# MultiWiiChassis_hex_power.net
KiCad netlist of a schematic drawn in EAGLE
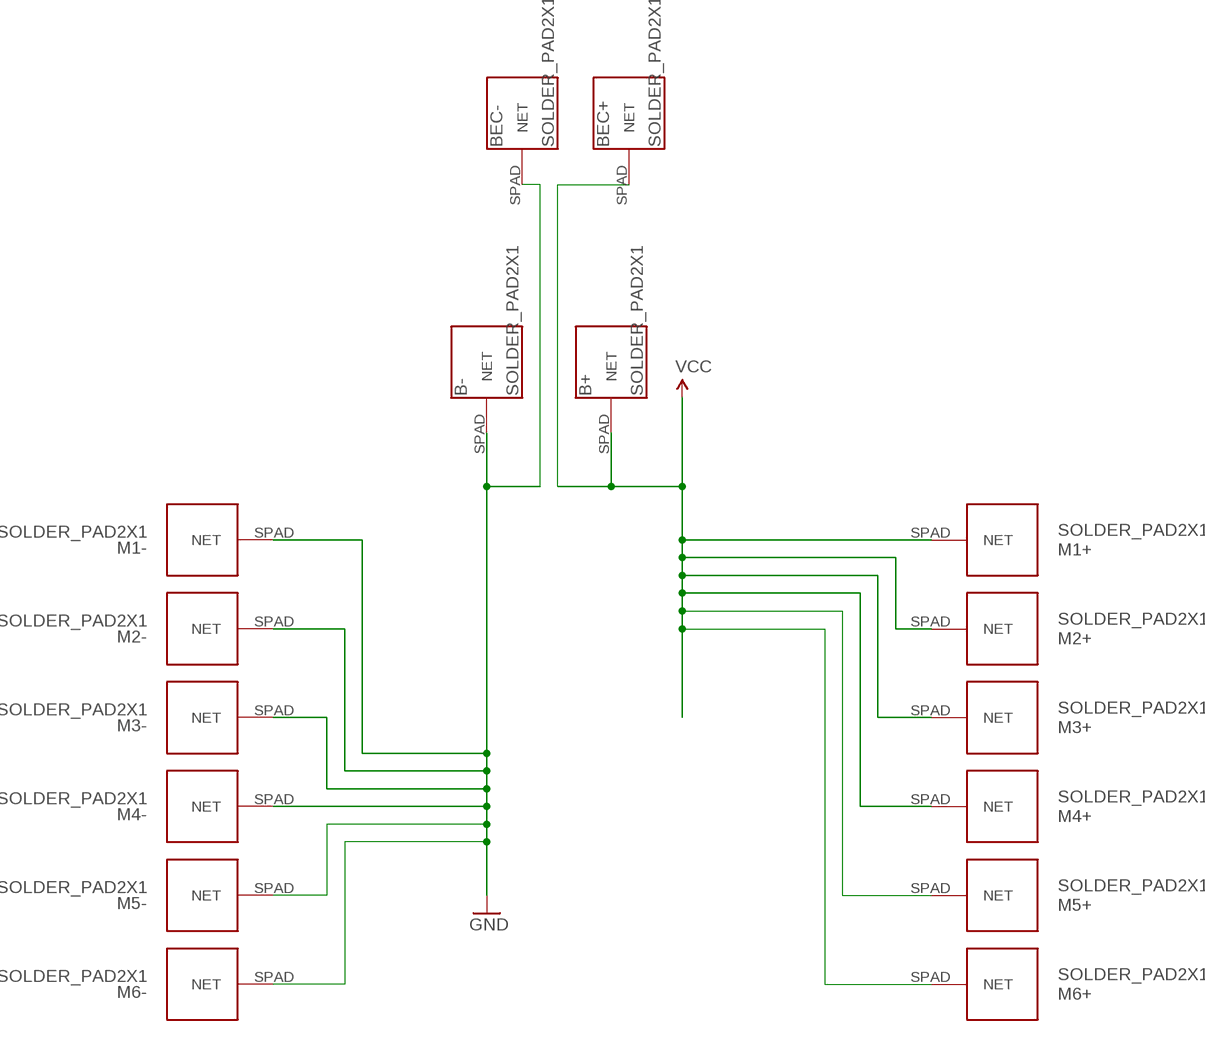
[diagram p0: schematic, sheet 1]

(export (version "E")
  (design (tool "Eeschema 10.0.6"))
  (components
    (comp (ref "B+")
      (value "SOLDER_PAD2X1")
      (footprint "eagle-import:SOLDER_PAD_2X1")
      (libsource (lib "eagle-import") (part "SOLDER_PAD2X1"))
    )
    (comp (ref "B-")
      (value "SOLDER_PAD2X1")
      (footprint "eagle-import:SOLDER_PAD_2X1")
      (libsource (lib "eagle-import") (part "SOLDER_PAD2X1"))
    )
    (comp (ref "BEC+")
      (value "SOLDER_PAD2X1")
      (footprint "eagle-import:SOLDER_PAD_2X1")
      (libsource (lib "eagle-import") (part "SOLDER_PAD2X1"))
    )
    (comp (ref "BEC-")
      (value "SOLDER_PAD2X1")
      (footprint "eagle-import:SOLDER_PAD_2X1")
      (libsource (lib "eagle-import") (part "SOLDER_PAD2X1"))
    )
    (comp (ref "M1+")
      (value "SOLDER_PAD2X1")
      (footprint "eagle-import:SOLDER_PAD_2X1")
      (libsource (lib "eagle-import") (part "SOLDER_PAD2X1"))
    )
    (comp (ref "M1-")
      (value "SOLDER_PAD2X1")
      (footprint "eagle-import:SOLDER_PAD_2X1")
      (libsource (lib "eagle-import") (part "SOLDER_PAD2X1"))
    )
    (comp (ref "M2+")
      (value "SOLDER_PAD2X1")
      (footprint "eagle-import:SOLDER_PAD_2X1")
      (libsource (lib "eagle-import") (part "SOLDER_PAD2X1"))
    )
    (comp (ref "M2-")
      (value "SOLDER_PAD2X1")
      (footprint "eagle-import:SOLDER_PAD_2X1")
      (libsource (lib "eagle-import") (part "SOLDER_PAD2X1"))
    )
    (comp (ref "M3+")
      (value "SOLDER_PAD2X1")
      (footprint "eagle-import:SOLDER_PAD_2X1")
      (libsource (lib "eagle-import") (part "SOLDER_PAD2X1"))
    )
    (comp (ref "M3-")
      (value "SOLDER_PAD2X1")
      (footprint "eagle-import:SOLDER_PAD_2X1")
      (libsource (lib "eagle-import") (part "SOLDER_PAD2X1"))
    )
    (comp (ref "M4+")
      (value "SOLDER_PAD2X1")
      (footprint "eagle-import:SOLDER_PAD_2X1")
      (libsource (lib "eagle-import") (part "SOLDER_PAD2X1"))
    )
    (comp (ref "M4-")
      (value "SOLDER_PAD2X1")
      (footprint "eagle-import:SOLDER_PAD_2X1")
      (libsource (lib "eagle-import") (part "SOLDER_PAD2X1"))
    )
    (comp (ref "M5+")
      (value "SOLDER_PAD2X1")
      (footprint "eagle-import:SOLDER_PAD_2X1")
      (libsource (lib "eagle-import") (part "SOLDER_PAD2X1"))
    )
    (comp (ref "M5-")
      (value "SOLDER_PAD2X1")
      (footprint "eagle-import:SOLDER_PAD_2X1")
      (libsource (lib "eagle-import") (part "SOLDER_PAD2X1"))
    )
    (comp (ref "M6+")
      (value "SOLDER_PAD2X1")
      (footprint "eagle-import:SOLDER_PAD_2X1")
      (libsource (lib "eagle-import") (part "SOLDER_PAD2X1"))
    )
    (comp (ref "M6-")
      (value "SOLDER_PAD2X1")
      (footprint "eagle-import:SOLDER_PAD_2X1")
      (libsource (lib "eagle-import") (part "SOLDER_PAD2X1"))
    )
  )
  (nets
    (net (code "1") (name "GND") (class "Default")
      (node (ref "B-") (pin "SPAD") (pinfunction "NET_SPAD") (pintype "bidirectional"))
      (node (ref "BEC-") (pin "SPAD") (pinfunction "NET_SPAD") (pintype "bidirectional"))
      (node (ref "M1-") (pin "SPAD") (pinfunction "NET_SPAD") (pintype "bidirectional"))
      (node (ref "M2-") (pin "SPAD") (pinfunction "NET_SPAD") (pintype "bidirectional"))
      (node (ref "M3-") (pin "SPAD") (pinfunction "NET_SPAD") (pintype "bidirectional"))
      (node (ref "M4-") (pin "SPAD") (pinfunction "NET_SPAD") (pintype "bidirectional"))
      (node (ref "M5-") (pin "SPAD") (pinfunction "NET_SPAD") (pintype "bidirectional"))
      (node (ref "M6-") (pin "SPAD") (pinfunction "NET_SPAD") (pintype "bidirectional"))
    )
    (net (code "2") (name "VCC") (class "Default")
      (node (ref "B+") (pin "SPAD") (pinfunction "NET_SPAD") (pintype "bidirectional"))
      (node (ref "BEC+") (pin "SPAD") (pinfunction "NET_SPAD") (pintype "bidirectional"))
      (node (ref "M1+") (pin "SPAD") (pinfunction "NET_SPAD") (pintype "bidirectional"))
      (node (ref "M2+") (pin "SPAD") (pinfunction "NET_SPAD") (pintype "bidirectional"))
      (node (ref "M3+") (pin "SPAD") (pinfunction "NET_SPAD") (pintype "bidirectional"))
      (node (ref "M4+") (pin "SPAD") (pinfunction "NET_SPAD") (pintype "bidirectional"))
      (node (ref "M5+") (pin "SPAD") (pinfunction "NET_SPAD") (pintype "bidirectional"))
      (node (ref "M6+") (pin "SPAD") (pinfunction "NET_SPAD") (pintype "bidirectional"))
    )
  )
)
